# Arduino_CAN_Dev_Board.net
KiCad netlist of a schematic drawn in EAGLE
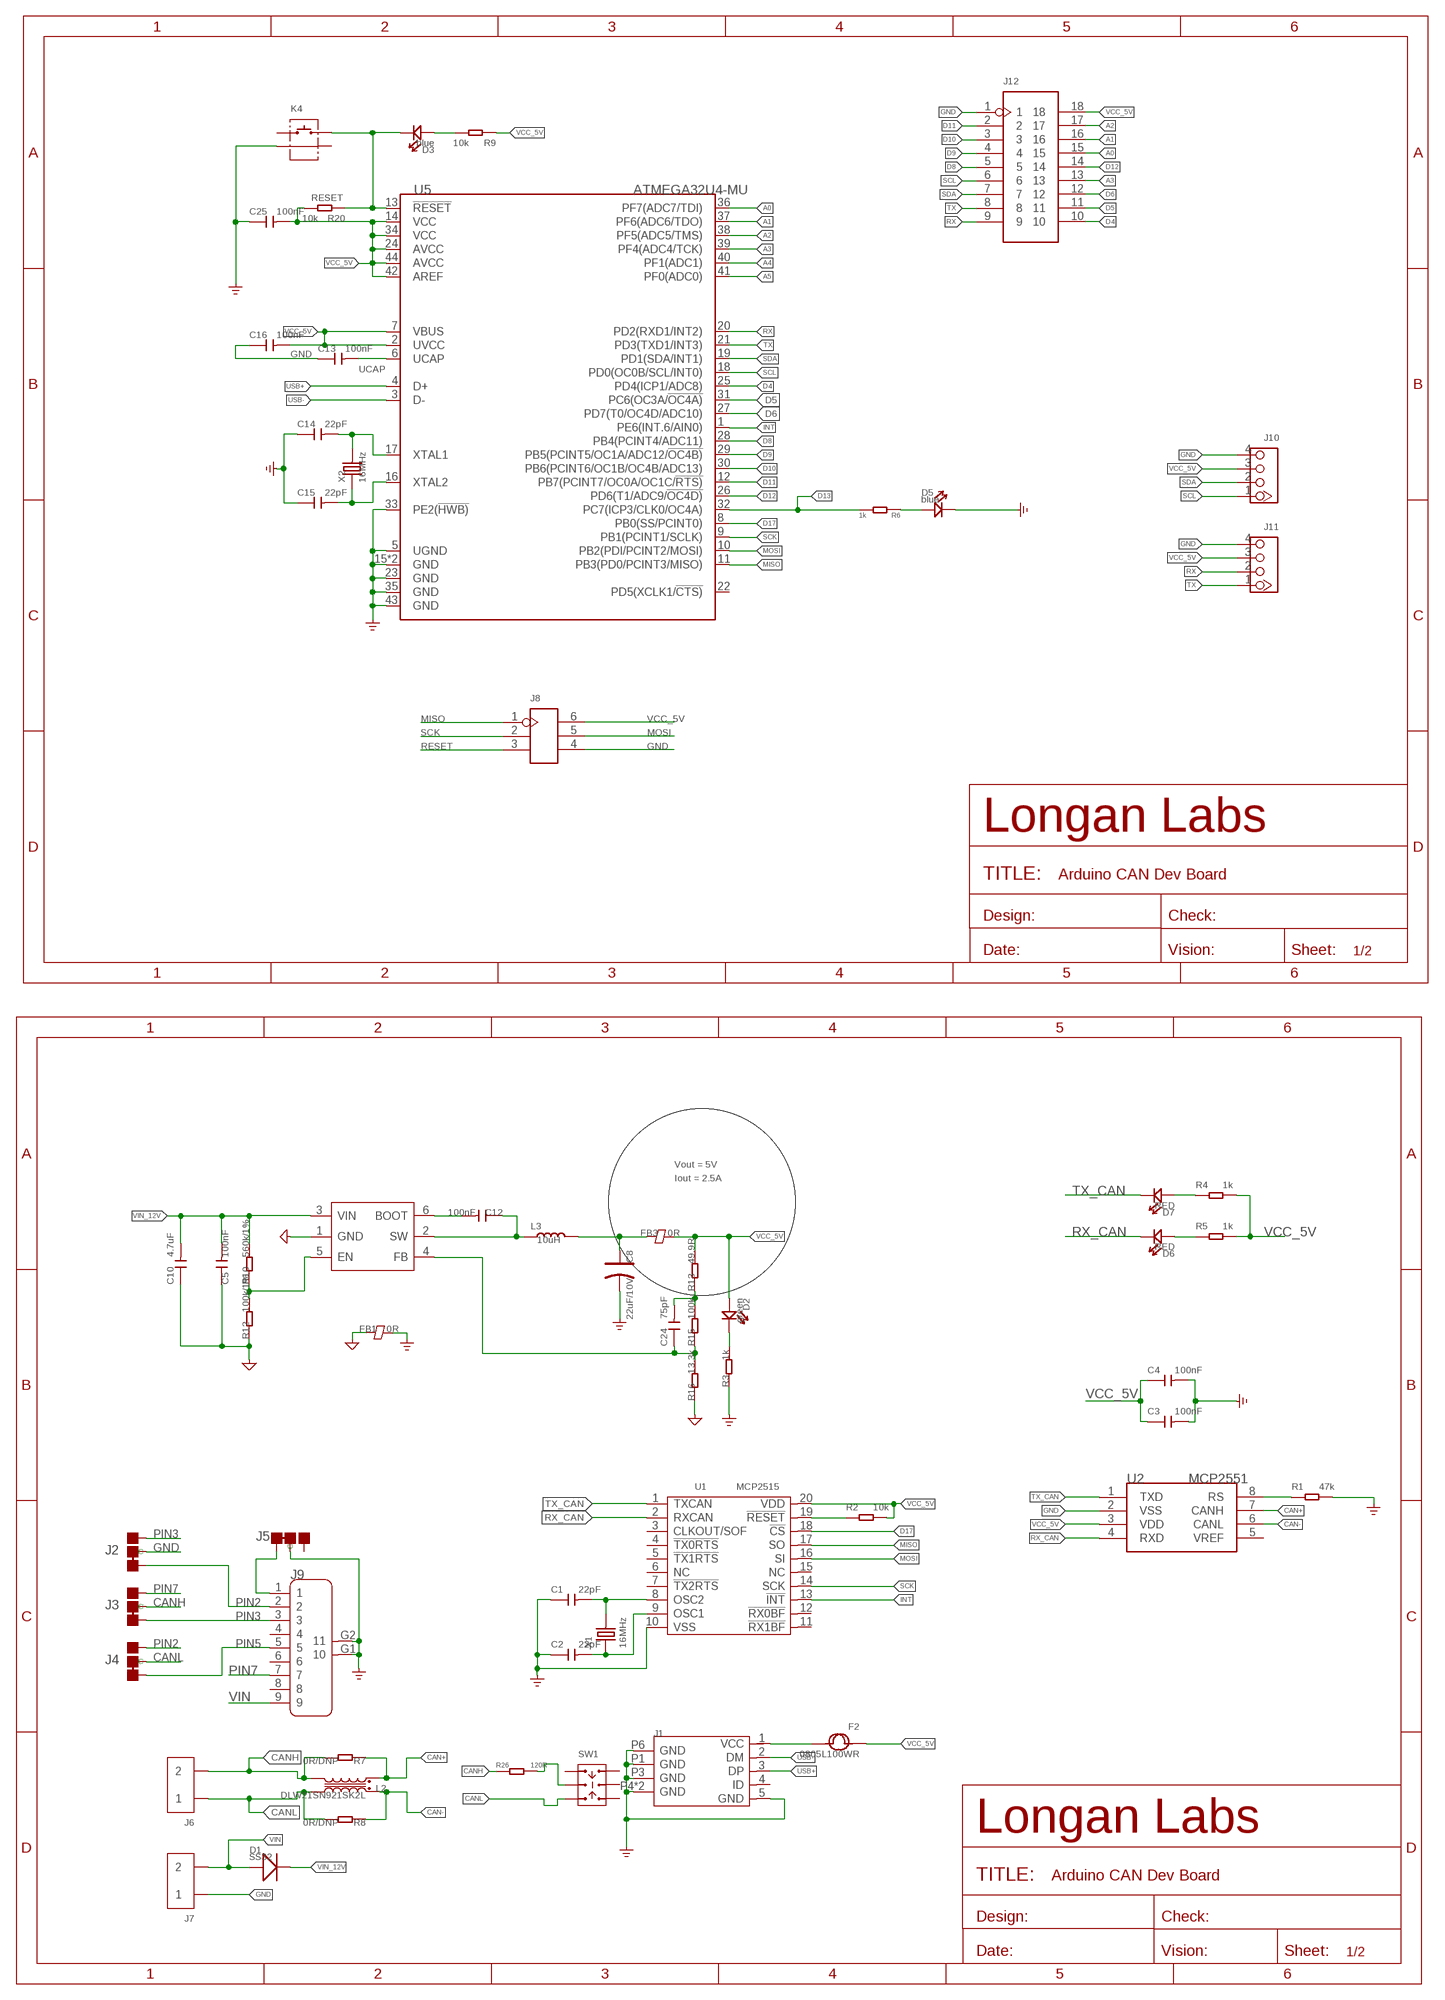
[diagram p0: schematic, sheet 1]

(export (version "E")
  (design (tool "Eeschema 10.0.6"))
  (components
    (comp (ref "C1")
      (value "22pF")
      (footprint "eagle-import:C0603")
      (libsource (lib "eagle-import") (part "CAP-0603"))
    )
    (comp (ref "C2")
      (value "22pF")
      (footprint "eagle-import:C0603")
      (libsource (lib "eagle-import") (part "CAP-0603"))
    )
    (comp (ref "C3")
      (value "100nF")
      (footprint "eagle-import:C0603")
      (libsource (lib "eagle-import") (part "CAP-0603"))
    )
    (comp (ref "C4")
      (value "100nF")
      (footprint "eagle-import:C0603")
      (libsource (lib "eagle-import") (part "CAP-0603"))
    )
    (comp (ref "C5")
      (value "100nF")
      (footprint "eagle-import:C0603")
      (libsource (lib "eagle-import") (part "CAP-0603"))
    )
    (comp (ref "C8")
      (value "22uF/10V")
      (footprint "eagle-import:AVX-B")
      (libsource (lib "eagle-import") (part "CAP-POLAR-AVX-B"))
    )
    (comp (ref "C10")
      (value "4.7uF")
      (footprint "eagle-import:C1206")
      (libsource (lib "eagle-import") (part "CAP-1206"))
    )
    (comp (ref "C12")
      (value "100nF")
      (footprint "eagle-import:C0603")
      (libsource (lib "eagle-import") (part "CAP-0603"))
    )
    (comp (ref "C13")
      (value "100nF")
      (footprint "eagle-import:C0603")
      (libsource (lib "eagle-import") (part "CAP-0603"))
    )
    (comp (ref "C14")
      (value "22pF")
      (footprint "eagle-import:C0603")
      (libsource (lib "eagle-import") (part "CAP-0603"))
    )
    (comp (ref "C15")
      (value "22pF")
      (footprint "eagle-import:C0603")
      (libsource (lib "eagle-import") (part "CAP-0603"))
    )
    (comp (ref "C16")
      (value "100nF")
      (footprint "eagle-import:C0603")
      (libsource (lib "eagle-import") (part "CAP-0603"))
    )
    (comp (ref "C24")
      (value "75pF")
      (footprint "eagle-import:C0603")
      (libsource (lib "eagle-import") (part "CAP-0603"))
    )
    (comp (ref "C25")
      (value "100nF")
      (footprint "eagle-import:C0603")
      (libsource (lib "eagle-import") (part "CAP-0603"))
    )
    (comp (ref "D1")
      (value "SS32")
      (footprint "eagle-import:DO-214AC")
      (libsource (lib "eagle-import") (part "DIODE'SMA'"))
    )
    (comp (ref "D2")
      (value "green")
      (footprint "eagle-import:LED-0603")
      (libsource (lib "eagle-import") (part "LED'0603'"))
    )
    (comp (ref "D3")
      (value "blue")
      (footprint "eagle-import:LED-0603")
      (libsource (lib "eagle-import") (part "LED'0603'"))
    )
    (comp (ref "D5")
      (value "blue")
      (footprint "eagle-import:LED-0603")
      (libsource (lib "eagle-import") (part "LED'0603'"))
    )
    (comp (ref "D6")
      (value "RED")
      (footprint "eagle-import:LED-0603")
      (libsource (lib "eagle-import") (part "LED'0603'"))
    )
    (comp (ref "D7")
      (value "RED")
      (footprint "eagle-import:LED-0603")
      (libsource (lib "eagle-import") (part "LED'0603'"))
    )
    (comp (ref "F2")
      (value "0805L100WR")
      (footprint "eagle-import:F0805")
      (libsource (lib "eagle-import") (part "FUSE0805"))
    )
    (comp (ref "FB1")
      (value "0R")
      (footprint "eagle-import:F0805")
      (libsource (lib "eagle-import") (part "FERRITE-BEAD-0805"))
    )
    (comp (ref "FB3")
      (value "0R")
      (footprint "eagle-import:F0805")
      (libsource (lib "eagle-import") (part "FERRITE-BEAD-0805"))
    )
    (comp (ref "J1")
      (value "MICRO-USB5+4P-320010050")
      (footprint "eagle-import:MICRO-USB5+5P-SMD-0.65-7.2X5.06MM")
      (libsource (lib "eagle-import") (part "MICRO-USB5+4P-320010050"))
    )
    (comp (ref "J2")
      (value "JUMPER-3P-SHORT")
      (footprint "eagle-import:3P-SMD-SHORT")
      (libsource (lib "eagle-import") (part "JUMPER-3P-SHORT"))
    )
    (comp (ref "J3")
      (value "JUMPER-3P-SHORT")
      (footprint "eagle-import:3P-SMD-SHORT")
      (libsource (lib "eagle-import") (part "JUMPER-3P-SHORT"))
    )
    (comp (ref "J4")
      (value "JUMPER-3P-SHORT")
      (footprint "eagle-import:3P-SMD-SHORT")
      (libsource (lib "eagle-import") (part "JUMPER-3P-SHORT"))
    )
    (comp (ref "J5")
      (value "JUMPER-3P-SHORT")
      (footprint "eagle-import:3P-SMD-SHORT")
      (libsource (lib "eagle-import") (part "JUMPER-3P-SHORT"))
    )
    (comp (ref "J6")
      (value "SCREW-TERMINAL-2P'5.08'")
      (footprint "eagle-import:H2-5.0-10.5X8.0MM")
      (libsource (lib "eagle-import") (part "SCREW-TERMINAL-2P'5.08'"))
    )
    (comp (ref "J7")
      (value "SCREW-TERMINAL-2P'5.08'")
      (footprint "eagle-import:H2-5.0-10.5X8.0MM")
      (libsource (lib "eagle-import") (part "SCREW-TERMINAL-2P'5.08'"))
    )
    (comp (ref "J8")
      (value "HEADER-2X3P-2.54")
      (footprint "eagle-import:H2X3-2.54")
      (libsource (lib "eagle-import") (part "HEADER-2X3P-2.54"))
    )
    (comp (ref "J9")
      (value "DB9'MEAL'")
      (footprint "eagle-import:DB9-MEAL")
      (libsource (lib "eagle-import") (part "DB9'MEAL'"))
    )
    (comp (ref "J10")
      (value "320110033")
      (footprint "eagle-import:HW4-2.0")
      (libsource (lib "eagle-import") (part "GROVE-CONNECTOR-DIP-2.0"))
    )
    (comp (ref "J11")
      (value "320110033")
      (footprint "eagle-import:HW4-2.0")
      (libsource (lib "eagle-import") (part "GROVE-CONNECTOR-DIP-2.0"))
    )
    (comp (ref "J12")
      (value "HEADER-2X9P-2.54")
      (footprint "eagle-import:H2X9-2.54")
      (libsource (lib "eagle-import") (part "HEADER-2X9P-2.54"))
    )
    (comp (ref "K4")
      (value "BUTTON-2+2P")
      (footprint "eagle-import:SW2+2P-7.7X2.75X3.95MM")
      (libsource (lib "eagle-import") (part "BUTTON-2+2P"))
    )
    (comp (ref "L2")
      (value "DLW21SN921SK2L")
      (footprint "eagle-import:INT4-0.85-2X1.25X1.2MM")
      (libsource (lib "eagle-import") (part "INDUCTOR-COMMON-MODE-SRF2012-900YA"))
    )
    (comp (ref "L3")
      (value "10uH")
      (footprint "eagle-import:INT2-SMD-6.6X7.1X3MM")
      (libsource (lib "eagle-import") (part "INDUCTOR-6.6X7.1"))
    )
    (comp (ref "R1")
      (value "47k")
      (footprint "eagle-import:R0603")
      (libsource (lib "eagle-import") (part "RES-0603"))
    )
    (comp (ref "R2")
      (value "10k")
      (footprint "eagle-import:R0603")
      (libsource (lib "eagle-import") (part "RES-0603"))
    )
    (comp (ref "R3")
      (value "1k")
      (footprint "eagle-import:R0603")
      (libsource (lib "eagle-import") (part "RES-0603"))
    )
    (comp (ref "R4")
      (value "1k")
      (footprint "eagle-import:R0603")
      (libsource (lib "eagle-import") (part "RES-0603"))
    )
    (comp (ref "R5")
      (value "1k")
      (footprint "eagle-import:R0603")
      (libsource (lib "eagle-import") (part "RES-0603"))
    )
    (comp (ref "R6")
      (value "1k")
      (footprint "eagle-import:R0603")
      (libsource (lib "eagle-import") (part "RES-0603"))
    )
    (comp (ref "R7")
      (value "0R/DNP")
      (footprint "eagle-import:R0603")
      (libsource (lib "eagle-import") (part "RES-0603"))
    )
    (comp (ref "R8")
      (value "0R/DNP")
      (footprint "eagle-import:R0603")
      (libsource (lib "eagle-import") (part "RES-0603"))
    )
    (comp (ref "R9")
      (value "10k")
      (footprint "eagle-import:R0603")
      (libsource (lib "eagle-import") (part "RES-0603"))
    )
    (comp (ref "R10")
      (value "560k/1%")
      (footprint "eagle-import:R0603")
      (libsource (lib "eagle-import") (part "RES-0603"))
    )
    (comp (ref "R12")
      (value "100k/1%")
      (footprint "eagle-import:R0603")
      (libsource (lib "eagle-import") (part "RES-0603"))
    )
    (comp (ref "R13")
      (value "49.9R")
      (footprint "eagle-import:R0603")
      (libsource (lib "eagle-import") (part "RES-0603"))
    )
    (comp (ref "R15")
      (value "100k")
      (footprint "eagle-import:R0603")
      (libsource (lib "eagle-import") (part "RES-0603"))
    )
    (comp (ref "R16")
      (value "13.3k")
      (footprint "eagle-import:R0603")
      (libsource (lib "eagle-import") (part "RES-0603"))
    )
    (comp (ref "R20")
      (value "10k")
      (footprint "eagle-import:R0603")
      (libsource (lib "eagle-import") (part "RES-0603"))
    )
    (comp (ref "R26")
      (value "120R")
      (footprint "eagle-import:R0603")
      (libsource (lib "eagle-import") (part "RES-0603"))
    )
    (comp (ref "SW1")
      (value "SWITCH-2CH-6P-311010004")
      (footprint "eagle-import:SW6-2.54-9.0X3.5X3.2+2.0MM")
      (libsource (lib "eagle-import") (part "SWITCH-2CH-6P-311010004"))
    )
    (comp (ref "U$11")
      (value "PMIC-TPS54302")
      (footprint "eagle-import:SOT-23-6")
      (libsource (lib "eagle-import") (part "PMIC-TPS54302"))
    )
    (comp (ref "U1")
      (value "MCP2515")
      (footprint "eagle-import:TSSOP20-0.65-6.5X4.4MM")
      (libsource (lib "eagle-import") (part "MCP2515'ST'"))
    )
    (comp (ref "U2")
      (value "MCP2551")
      (footprint "eagle-import:SOIC8-6.0")
      (libsource (lib "eagle-import") (part "MCP2551-SOIC8"))
    )
    (comp (ref "U5")
      (value "ATMEGA32U4-MU")
      (footprint "eagle-import:QFN44")
      (libsource (lib "eagle-import") (part "ATMEGA32U4-MU"))
    )
    (comp (ref "X1")
      (value "16MHz")
      (footprint "eagle-import:X2-SMD-5.0X3.2X1.3MM")
      (libsource (lib "eagle-import") (part "CRYSTAL-2P'5032'"))
    )
    (comp (ref "X2")
      (value "16MHz")
      (footprint "eagle-import:2P-SMD-5X3.2")
      (libsource (lib "eagle-import") (part "CRYSTAL'5032'"))
    )
  )
  (nets
    (net (code "1") (name "A0") (class "Default")
      (node (ref "J12") (pin "15") (pinfunction "15_15") (pintype "bidirectional"))
      (node (ref "U5") (pin "36") (pinfunction "PF7(ADC7/TDI)_36") (pintype "bidirectional"))
    )
    (net (code "2") (name "A1") (class "Default")
      (node (ref "J12") (pin "16") (pinfunction "16_16") (pintype "bidirectional"))
      (node (ref "U5") (pin "37") (pinfunction "PF6(ADC6/TDO)_37") (pintype "bidirectional"))
    )
    (net (code "3") (name "A2") (class "Default")
      (node (ref "J12") (pin "17") (pinfunction "17_17") (pintype "bidirectional"))
      (node (ref "U5") (pin "38") (pinfunction "PF5(ADC5/TMS)_38") (pintype "bidirectional"))
    )
    (net (code "4") (name "A3") (class "Default")
      (node (ref "J12") (pin "13") (pinfunction "13_13") (pintype "bidirectional"))
      (node (ref "U5") (pin "39") (pinfunction "PF4(ADC4/TCK)_39") (pintype "bidirectional"))
    )
    (net (code "5") (name "A4") (class "Default")
      (node (ref "U5") (pin "40") (pinfunction "PF1(ADC1)_40") (pintype "bidirectional"))
    )
    (net (code "6") (name "A5") (class "Default")
      (node (ref "U5") (pin "41") (pinfunction "PF0(ADC0)_41") (pintype "bidirectional"))
    )
    (net (code "7") (name "AGND") (class "Default")
      (node (ref "C10") (pin "1") (pinfunction "1_1") (pintype "passive"))
      (node (ref "C5") (pin "1") (pinfunction "1_1") (pintype "passive"))
      (node (ref "FB1") (pin "1") (pinfunction "1_1") (pintype "bidirectional"))
      (node (ref "R12") (pin "1") (pinfunction "1_1") (pintype "passive"))
      (node (ref "R16") (pin "1") (pinfunction "1_1") (pintype "passive"))
      (node (ref "U$11") (pin "1") (pinfunction "GND_1") (pintype "bidirectional"))
    )
    (net (code "8") (name "CAN+") (class "Default")
      (node (ref "L2") (pin "4") (pinfunction "4_4") (pintype "bidirectional"))
      (node (ref "R7") (pin "1") (pinfunction "1_1") (pintype "passive"))
      (node (ref "U2") (pin "7") (pinfunction "CANH_7") (pintype "bidirectional"))
    )
    (net (code "9") (name "CAN-") (class "Default")
      (node (ref "L2") (pin "1") (pinfunction "1_1") (pintype "bidirectional"))
      (node (ref "R8") (pin "1") (pinfunction "1_1") (pintype "passive"))
      (node (ref "U2") (pin "6") (pinfunction "CANL_6") (pintype "bidirectional"))
    )
    (net (code "10") (name "CANH") (class "Default")
      (node (ref "J3") (pin "MM") (pinfunction "C_MM") (pintype "bidirectional"))
      (node (ref "J6") (pin "2") (pinfunction "2_2") (pintype "bidirectional"))
      (node (ref "L2") (pin "3") (pinfunction "3_3") (pintype "bidirectional"))
      (node (ref "R26") (pin "1") (pinfunction "1_1") (pintype "passive"))
      (node (ref "R7") (pin "2") (pinfunction "2_2") (pintype "passive"))
    )
    (net (code "11") (name "CANL") (class "Default")
      (node (ref "J4") (pin "MM") (pinfunction "C_MM") (pintype "bidirectional"))
      (node (ref "J6") (pin "1") (pinfunction "1_1") (pintype "bidirectional"))
      (node (ref "L2") (pin "2") (pinfunction "2_2") (pintype "bidirectional"))
      (node (ref "R8") (pin "2") (pinfunction "2_2") (pintype "passive"))
      (node (ref "SW1") (pin "CH1B") (pinfunction "CH1B_CH1B") (pintype "bidirectional"))
    )
    (net (code "12") (name "D4") (class "Default")
      (node (ref "J12") (pin "10") (pinfunction "10_10") (pintype "bidirectional"))
      (node (ref "U5") (pin "25") (pinfunction "PD4(ICP1/ADC8)_25") (pintype "bidirectional"))
    )
    (net (code "13") (name "D5") (class "Default")
      (node (ref "J12") (pin "11") (pinfunction "11_11") (pintype "bidirectional"))
      (node (ref "U5") (pin "31") (pinfunction "PC6(OC3A/~{OC4A})_31") (pintype "bidirectional"))
    )
    (net (code "14") (name "D6") (class "Default")
      (node (ref "J12") (pin "12") (pinfunction "12_12") (pintype "bidirectional"))
      (node (ref "U5") (pin "27") (pinfunction "PD7(T0/OC4D/ADC10)_27") (pintype "bidirectional"))
    )
    (net (code "15") (name "D8") (class "Default")
      (node (ref "J12") (pin "5") (pinfunction "5_5") (pintype "bidirectional"))
      (node (ref "U5") (pin "28") (pinfunction "PB4(PCINT4/ADC11)_28") (pintype "bidirectional"))
    )
    (net (code "16") (name "D9") (class "Default")
      (node (ref "J12") (pin "4") (pinfunction "4_4") (pintype "bidirectional"))
      (node (ref "U5") (pin "29") (pinfunction "PB5(PCINT5/OC1A/ADC12/~{OC4B})_29") (pintype "bidirectional"))
    )
    (net (code "17") (name "D10") (class "Default")
      (node (ref "J12") (pin "3") (pinfunction "3_3") (pintype "bidirectional"))
      (node (ref "U5") (pin "30") (pinfunction "PB6(PCINT6/OC1B/OC4B/ADC13)_30") (pintype "bidirectional"))
    )
    (net (code "18") (name "D11") (class "Default")
      (node (ref "J12") (pin "2") (pinfunction "2_2") (pintype "bidirectional"))
      (node (ref "U5") (pin "12") (pinfunction "PB7(PCINT7/OC0A/OC1C/~{RTS})_12") (pintype "bidirectional"))
    )
    (net (code "19") (name "D12") (class "Default")
      (node (ref "J12") (pin "14") (pinfunction "14_14") (pintype "bidirectional"))
      (node (ref "U5") (pin "26") (pinfunction "PD6(T1/ADC9/~{OC4D})_26") (pintype "bidirectional"))
    )
    (net (code "20") (name "D13") (class "Default")
      (node (ref "R6") (pin "2") (pinfunction "2_2") (pintype "passive"))
      (node (ref "U5") (pin "32") (pinfunction "PC7(ICP3/CLK0/OC4A)_32") (pintype "bidirectional"))
    )
    (net (code "21") (name "D17") (class "Default")
      (node (ref "U1") (pin "18") (pinfunction "~{CS}_18") (pintype "bidirectional"))
      (node (ref "U5") (pin "8") (pinfunction "PB0(SS/PCINT0)_8") (pintype "bidirectional"))
    )
    (net (code "22") (name "GND") (class "Default")
      (node (ref "C1") (pin "1") (pinfunction "1_1") (pintype "passive"))
      (node (ref "C13") (pin "1") (pinfunction "1_1") (pintype "passive"))
      (node (ref "C14") (pin "1") (pinfunction "1_1") (pintype "passive"))
      (node (ref "C15") (pin "1") (pinfunction "1_1") (pintype "passive"))
      (node (ref "C16") (pin "1") (pinfunction "1_1") (pintype "passive"))
      (node (ref "C2") (pin "1") (pinfunction "1_1") (pintype "passive"))
      (node (ref "C25") (pin "1") (pinfunction "1_1") (pintype "passive"))
      (node (ref "C3") (pin "2") (pinfunction "2_2") (pintype "passive"))
      (node (ref "C4") (pin "2") (pinfunction "2_2") (pintype "passive"))
      (node (ref "C8") (pin "-") (pinfunction "-_-") (pintype "passive"))
      (node (ref "D5") (pin "-") (pinfunction "-_-") (pintype "passive"))
      (node (ref "FB1") (pin "2") (pinfunction "2_2") (pintype "bidirectional"))
      (node (ref "J1") (pin "5") (pinfunction "GND_5") (pintype "bidirectional"))
      (node (ref "J1") (pin "P1") (pinfunction "GND_P1") (pintype "bidirectional"))
      (node (ref "J1") (pin "P3") (pinfunction "GND_P3") (pintype "bidirectional"))
      (node (ref "J1") (pin "P4") (pinfunction "GND_P4") (pintype "bidirectional"))
      (node (ref "J1") (pin "P5") (pinfunction "GND_P5") (pintype "bidirectional"))
      (node (ref "J1") (pin "P6") (pinfunction "GND_P6") (pintype "bidirectional"))
      (node (ref "J10") (pin "4") (pinfunction "4_4") (pintype "bidirectional"))
      (node (ref "J11") (pin "4") (pinfunction "4_4") (pintype "bidirectional"))
      (node (ref "J12") (pin "1") (pinfunction "1_1") (pintype "bidirectional"))
      (node (ref "J2") (pin "MM") (pinfunction "C_MM") (pintype "bidirectional"))
      (node (ref "J5") (pin "MM") (pinfunction "C_MM") (pintype "bidirectional"))
      (node (ref "J7") (pin "1") (pinfunction "1_1") (pintype "bidirectional"))
      (node (ref "J8") (pin "4") (pinfunction "4_4") (pintype "bidirectional"))
      (node (ref "J9") (pin "G1") (pinfunction "10_G1") (pintype "bidirectional"))
      (node (ref "J9") (pin "G2") (pinfunction "11_G2") (pintype "bidirectional"))
      (node (ref "K4") (pin "S1") (pinfunction "S1_S1") (pintype "bidirectional"))
      (node (ref "R1") (pin "2") (pinfunction "2_2") (pintype "passive"))
      (node (ref "R3") (pin "1") (pinfunction "1_1") (pintype "passive"))
      (node (ref "U1") (pin "10") (pinfunction "VSS_10") (pintype "bidirectional"))
      (node (ref "U2") (pin "2") (pinfunction "VSS_2") (pintype "bidirectional"))
      (node (ref "U5") (pin "15") (pinfunction "GND_15") (pintype "bidirectional"))
      (node (ref "U5") (pin "23") (pinfunction "GND_23") (pintype "bidirectional"))
      (node (ref "U5") (pin "33") (pinfunction "PE2(~{HWB})_33") (pintype "bidirectional"))
      (node (ref "U5") (pin "35") (pinfunction "GND_35") (pintype "bidirectional"))
      (node (ref "U5") (pin "43") (pinfunction "GND_43") (pintype "bidirectional"))
      (node (ref "U5") (pin "5") (pinfunction "UGND_5") (pintype "bidirectional"))
      (node (ref "U5") (pin "TAB") (pinfunction "GND_TAB") (pintype "bidirectional"))
    )
    (net (code "23") (name "INT") (class "Default")
      (node (ref "U1") (pin "13") (pinfunction "~{INT}_13") (pintype "bidirectional"))
      (node (ref "U5") (pin "1") (pinfunction "PE6(INT.6/AIN0)_1") (pintype "bidirectional"))
    )
    (net (code "24") (name "MISO") (class "Default")
      (node (ref "J8") (pin "1") (pinfunction "1_1") (pintype "bidirectional"))
      (node (ref "U1") (pin "17") (pinfunction "SO_17") (pintype "bidirectional"))
      (node (ref "U5") (pin "11") (pinfunction "PB3(PD0/PCINT3/MISO)_11") (pintype "bidirectional"))
    )
    (net (code "25") (name "MOSI") (class "Default")
      (node (ref "J8") (pin "5") (pinfunction "5_5") (pintype "bidirectional"))
      (node (ref "U1") (pin "16") (pinfunction "SI_16") (pintype "bidirectional"))
      (node (ref "U5") (pin "10") (pinfunction "PB2(PDI/PCINT2/MOSI)_10") (pintype "bidirectional"))
    )
    (net (code "26") (name "Net-(C8-Pad+)") (class "Default")
      (node (ref "C8") (pin "+") (pinfunction "+_+") (pintype "passive"))
      (node (ref "FB3") (pin "1") (pinfunction "1_1") (pintype "bidirectional"))
      (node (ref "L3") (pin "2") (pinfunction "2_2") (pintype "passive"))
    )
    (net (code "27") (name "Net-(C24-Pad2)") (class "Default")
      (node (ref "C24") (pin "2") (pinfunction "2_2") (pintype "passive"))
      (node (ref "R13") (pin "1") (pinfunction "1_1") (pintype "passive"))
      (node (ref "R15") (pin "2") (pinfunction "2_2") (pintype "passive"))
    )
    (net (code "28") (name "Net-(D2-Pad-)") (class "Default")
      (node (ref "D2") (pin "-") (pinfunction "-_-") (pintype "passive"))
      (node (ref "R3") (pin "2") (pinfunction "2_2") (pintype "passive"))
    )
    (net (code "29") (name "Net-(D3-Pad+)") (class "Default")
      (node (ref "D3") (pin "+") (pinfunction "+_+") (pintype "passive"))
      (node (ref "R9") (pin "2") (pinfunction "2_2") (pintype "passive"))
    )
    (net (code "30") (name "Net-(D5-Pad+)") (class "Default")
      (node (ref "D5") (pin "+") (pinfunction "+_+") (pintype "passive"))
      (node (ref "R6") (pin "1") (pinfunction "1_1") (pintype "passive"))
    )
    (net (code "31") (name "Net-(D6-Pad+)") (class "Default")
      (node (ref "D6") (pin "+") (pinfunction "+_+") (pintype "passive"))
      (node (ref "R5") (pin "1") (pinfunction "1_1") (pintype "passive"))
    )
    (net (code "32") (name "Net-(D7-Pad+)") (class "Default")
      (node (ref "D7") (pin "+") (pinfunction "+_+") (pintype "passive"))
      (node (ref "R4") (pin "1") (pinfunction "1_1") (pintype "passive"))
    )
    (net (code "33") (name "Net-(J1-VCC)") (class "Default")
      (node (ref "F2") (pin "2") (pinfunction "2_2") (pintype "bidirectional"))
      (node (ref "J1") (pin "1") (pinfunction "VCC_1") (pintype "bidirectional"))
    )
    (net (code "34") (name "Net-(J5-L)") (class "Default")
      (node (ref "J5") (pin "11") (pinfunction "L_11") (pintype "bidirectional"))
      (node (ref "J9") (pin "1") (pinfunction "1_1") (pintype "bidirectional"))
    )
    (net (code "35") (name "Net-(R26-Pad2)") (class "Default")
      (node (ref "R26") (pin "2") (pinfunction "2_2") (pintype "passive"))
      (node (ref "SW1") (pin "COM1") (pinfunction "COM1_COM1") (pintype "bidirectional"))
    )
    (net (code "36") (name "Net-(U$11-BOOT)") (class "Default")
      (node (ref "C12") (pin "2") (pinfunction "2_2") (pintype "passive"))
      (node (ref "U$11") (pin "6") (pinfunction "BOOT_6") (pintype "bidirectional"))
    )
    (net (code "37") (name "Net-(U$11-EN)") (class "Default")
      (node (ref "R10") (pin "1") (pinfunction "1_1") (pintype "passive"))
      (node (ref "R12") (pin "2") (pinfunction "2_2") (pintype "passive"))
      (node (ref "U$11") (pin "5") (pinfunction "EN_5") (pintype "bidirectional"))
    )
    (net (code "38") (name "Net-(U$11-FB)") (class "Default")
      (node (ref "C24") (pin "1") (pinfunction "1_1") (pintype "passive"))
      (node (ref "R15") (pin "1") (pinfunction "1_1") (pintype "passive"))
      (node (ref "R16") (pin "2") (pinfunction "2_2") (pintype "passive"))
      (node (ref "U$11") (pin "4") (pinfunction "FB_4") (pintype "bidirectional"))
    )
    (net (code "39") (name "Net-(U$11-SW)") (class "Default")
      (node (ref "C12") (pin "1") (pinfunction "1_1") (pintype "passive"))
      (node (ref "L3") (pin "1") (pinfunction "1_1") (pintype "passive"))
      (node (ref "U$11") (pin "2") (pinfunction "SW_2") (pintype "bidirectional"))
    )
    (net (code "40") (name "Net-(U1-OSC1)") (class "Default")
      (node (ref "C2") (pin "2") (pinfunction "2_2") (pintype "passive"))
      (node (ref "U1") (pin "9") (pinfunction "OSC1_9") (pintype "bidirectional"))
      (node (ref "X1") (pin "1") (pinfunction "1_1") (pintype "passive"))
    )
    (net (code "41") (name "Net-(U1-OSC2)") (class "Default")
      (node (ref "C1") (pin "2") (pinfunction "2_2") (pintype "passive"))
      (node (ref "U1") (pin "8") (pinfunction "OSC2_8") (pintype "bidirectional"))
      (node (ref "X1") (pin "2") (pinfunction "2_2") (pintype "passive"))
    )
    (net (code "42") (name "Net-(U1-~{RESET})") (class "Default")
      (node (ref "R2") (pin "1") (pinfunction "1_1") (pintype "passive"))
      (node (ref "U1") (pin "19") (pinfunction "~{RESET}_19") (pintype "bidirectional"))
    )
    (net (code "43") (name "Net-(U2-RS)") (class "Default")
      (node (ref "R1") (pin "1") (pinfunction "1_1") (pintype "passive"))
      (node (ref "U2") (pin "8") (pinfunction "RS_8") (pintype "bidirectional"))
    )
    (net (code "44") (name "Net-(U5-XTAL1)") (class "Default")
      (node (ref "C14") (pin "2") (pinfunction "2_2") (pintype "passive"))
      (node (ref "U5") (pin "17") (pinfunction "XTAL1_17") (pintype "bidirectional"))
      (node (ref "X2") (pin "2") (pinfunction "2_2") (pintype "passive"))
    )
    (net (code "45") (name "Net-(U5-XTAL2)") (class "Default")
      (node (ref "C15") (pin "2") (pinfunction "2_2") (pintype "passive"))
      (node (ref "U5") (pin "16") (pinfunction "XTAL2_16") (pintype "bidirectional"))
      (node (ref "X2") (pin "1") (pinfunction "1_1") (pintype "passive"))
    )
    (net (code "46") (name "PIN2") (class "Default")
      (node (ref "J2") (pin "11") (pinfunction "L_11") (pintype "bidirectional"))
      (node (ref "J4") (pin "00") (pinfunction "R_00") (pintype "bidirectional"))
      (node (ref "J9") (pin "2") (pinfunction "2_2") (pintype "bidirectional"))
    )
    (net (code "47") (name "PIN3") (class "Default")
      (node (ref "J2") (pin "00") (pinfunction "R_00") (pintype "bidirectional"))
      (node (ref "J3") (pin "11") (pinfunction "L_11") (pintype "bidirectional"))
      (node (ref "J9") (pin "3") (pinfunction "3_3") (pintype "bidirectional"))
    )
    (net (code "48") (name "PIN5") (class "Default")
      (node (ref "J4") (pin "11") (pinfunction "L_11") (pintype "bidirectional"))
      (node (ref "J9") (pin "5") (pinfunction "5_5") (pintype "bidirectional"))
    )
    (net (code "49") (name "PIN7") (class "Default")
      (node (ref "J3") (pin "00") (pinfunction "R_00") (pintype "bidirectional"))
      (node (ref "J9") (pin "7") (pinfunction "7_7") (pintype "bidirectional"))
    )
    (net (code "50") (name "RESET") (class "Default")
      (node (ref "D3") (pin "-") (pinfunction "-_-") (pintype "passive"))
      (node (ref "J8") (pin "3") (pinfunction "3_3") (pintype "bidirectional"))
      (node (ref "K4") (pin "2") (pinfunction "2_2") (pintype "bidirectional"))
      (node (ref "R20") (pin "1") (pinfunction "1_1") (pintype "passive"))
      (node (ref "U5") (pin "13") (pinfunction "~{RESET}_13") (pintype "bidirectional"))
    )
    (net (code "51") (name "RX") (class "Default")
      (node (ref "J11") (pin "2") (pinfunction "2_2") (pintype "bidirectional"))
      (node (ref "J12") (pin "9") (pinfunction "9_9") (pintype "bidirectional"))
      (node (ref "U5") (pin "20") (pinfunction "PD2(RXD1/INT2)_20") (pintype "bidirectional"))
    )
    (net (code "52") (name "RX_CAN") (class "Default")
      (node (ref "D6") (pin "-") (pinfunction "-_-") (pintype "passive"))
      (node (ref "U1") (pin "2") (pinfunction "RXCAN_2") (pintype "bidirectional"))
      (node (ref "U2") (pin "4") (pinfunction "RXD_4") (pintype "bidirectional"))
    )
    (net (code "53") (name "SCK") (class "Default")
      (node (ref "J8") (pin "2") (pinfunction "2_2") (pintype "bidirectional"))
      (node (ref "U1") (pin "14") (pinfunction "SCK_14") (pintype "bidirectional"))
      (node (ref "U5") (pin "9") (pinfunction "PB1(PCINT1/SCLK)_9") (pintype "bidirectional"))
    )
    (net (code "54") (name "SCL") (class "Default")
      (node (ref "J10") (pin "1") (pinfunction "1_1") (pintype "bidirectional"))
      (node (ref "J12") (pin "6") (pinfunction "6_6") (pintype "bidirectional"))
      (node (ref "U5") (pin "18") (pinfunction "PD0(OC0B/SCL/INT0)_18") (pintype "bidirectional"))
    )
    (net (code "55") (name "SDA") (class "Default")
      (node (ref "J10") (pin "2") (pinfunction "2_2") (pintype "bidirectional"))
      (node (ref "J12") (pin "7") (pinfunction "7_7") (pintype "bidirectional"))
      (node (ref "U5") (pin "19") (pinfunction "PD1(SDA/INT1)_19") (pintype "bidirectional"))
    )
    (net (code "56") (name "TX") (class "Default")
      (node (ref "J11") (pin "1") (pinfunction "1_1") (pintype "bidirectional"))
      (node (ref "J12") (pin "8") (pinfunction "8_8") (pintype "bidirectional"))
      (node (ref "U5") (pin "21") (pinfunction "PD3(TXD1/INT3)_21") (pintype "bidirectional"))
    )
    (net (code "57") (name "TX_CAN") (class "Default")
      (node (ref "D7") (pin "-") (pinfunction "-_-") (pintype "passive"))
      (node (ref "U1") (pin "1") (pinfunction "TXCAN_1") (pintype "bidirectional"))
      (node (ref "U2") (pin "1") (pinfunction "TXD_1") (pintype "bidirectional"))
    )
    (net (code "58") (name "UCAP") (class "Default")
      (node (ref "C13") (pin "2") (pinfunction "2_2") (pintype "passive"))
      (node (ref "U5") (pin "6") (pinfunction "UCAP_6") (pintype "bidirectional"))
    )
    (net (code "59") (name "USB+") (class "Default")
      (node (ref "J1") (pin "3") (pinfunction "DP_3") (pintype "bidirectional"))
      (node (ref "U5") (pin "4") (pinfunction "D+_4") (pintype "bidirectional"))
    )
    (net (code "60") (name "USB-") (class "Default")
      (node (ref "J1") (pin "2") (pinfunction "DM_2") (pintype "bidirectional"))
      (node (ref "U5") (pin "3") (pinfunction "D-_3") (pintype "bidirectional"))
    )
    (net (code "61") (name "VCC_5V") (class "Default")
      (node (ref "C16") (pin "2") (pinfunction "2_2") (pintype "passive"))
      (node (ref "C25") (pin "2") (pinfunction "2_2") (pintype "passive"))
      (node (ref "C3") (pin "1") (pinfunction "1_1") (pintype "passive"))
      (node (ref "C4") (pin "1") (pinfunction "1_1") (pintype "passive"))
      (node (ref "D2") (pin "+") (pinfunction "+_+") (pintype "passive"))
      (node (ref "F2") (pin "1") (pinfunction "1_1") (pintype "bidirectional"))
      (node (ref "FB3") (pin "2") (pinfunction "2_2") (pintype "bidirectional"))
      (node (ref "J10") (pin "3") (pinfunction "3_3") (pintype "bidirectional"))
      (node (ref "J11") (pin "3") (pinfunction "3_3") (pintype "bidirectional"))
      (node (ref "J12") (pin "18") (pinfunction "18_18") (pintype "bidirectional"))
      (node (ref "J8") (pin "6") (pinfunction "6_6") (pintype "bidirectional"))
      (node (ref "R13") (pin "2") (pinfunction "2_2") (pintype "passive"))
      (node (ref "R2") (pin "2") (pinfunction "2_2") (pintype "passive"))
      (node (ref "R20") (pin "2") (pinfunction "2_2") (pintype "passive"))
      (node (ref "R4") (pin "2") (pinfunction "2_2") (pintype "passive"))
      (node (ref "R5") (pin "2") (pinfunction "2_2") (pintype "passive"))
      (node (ref "R9") (pin "1") (pinfunction "1_1") (pintype "passive"))
      (node (ref "U1") (pin "20") (pinfunction "VDD_20") (pintype "bidirectional"))
      (node (ref "U2") (pin "3") (pinfunction "VDD_3") (pintype "bidirectional"))
      (node (ref "U5") (pin "14") (pinfunction "VCC_14") (pintype "bidirectional"))
      (node (ref "U5") (pin "2") (pinfunction "UVCC_2") (pintype "bidirectional"))
      (node (ref "U5") (pin "24") (pinfunction "AVCC_24") (pintype "bidirectional"))
      (node (ref "U5") (pin "34") (pinfunction "VCC_34") (pintype "bidirectional"))
      (node (ref "U5") (pin "42") (pinfunction "AREF_42") (pintype "bidirectional"))
      (node (ref "U5") (pin "44") (pinfunction "AVCC_44") (pintype "bidirectional"))
      (node (ref "U5") (pin "7") (pinfunction "VBUS_7") (pintype "bidirectional"))
    )
    (net (code "62") (name "VIN") (class "Default")
      (node (ref "D1") (pin "1") (pinfunction "+_1") (pintype "passive"))
      (node (ref "J7") (pin "2") (pinfunction "2_2") (pintype "bidirectional"))
      (node (ref "J9") (pin "9") (pinfunction "9_9") (pintype "bidirectional"))
    )
    (net (code "63") (name "VIN_12V") (class "Default")
      (node (ref "C10") (pin "2") (pinfunction "2_2") (pintype "passive"))
      (node (ref "C5") (pin "2") (pinfunction "2_2") (pintype "passive"))
      (node (ref "D1") (pin "2") (pinfunction "-_2") (pintype "passive"))
      (node (ref "R10") (pin "2") (pinfunction "2_2") (pintype "passive"))
      (node (ref "U$11") (pin "3") (pinfunction "VIN_3") (pintype "bidirectional"))
    )
    (net (code "64") (name "unconnected-(J1-ID-Pad4)") (class "Default")
      (node (ref "J1") (pin "4") (pinfunction "ID_4") (pintype "bidirectional"))
    )
    (net (code "65") (name "unconnected-(J5-R-Pad00)") (class "Default")
      (node (ref "J5") (pin "00") (pinfunction "R_00") (pintype "bidirectional"))
    )
    (net (code "66") (name "unconnected-(J9-Pad4)") (class "Default")
      (node (ref "J9") (pin "4") (pinfunction "4_4") (pintype "bidirectional"))
    )
    (net (code "67") (name "unconnected-(J9-Pad6)") (class "Default")
      (node (ref "J9") (pin "6") (pinfunction "6_6") (pintype "bidirectional"))
    )
    (net (code "68") (name "unconnected-(J9-Pad8)") (class "Default")
      (node (ref "J9") (pin "8") (pinfunction "8_8") (pintype "bidirectional"))
    )
    (net (code "69") (name "unconnected-(K4-Pad1)") (class "Default")
      (node (ref "K4") (pin "1") (pinfunction "1_1") (pintype "bidirectional"))
    )
    (net (code "70") (name "unconnected-(K4-PadS2)") (class "Default")
      (node (ref "K4") (pin "S2") (pinfunction "S2_S2") (pintype "bidirectional"))
    )
    (net (code "71") (name "unconnected-(SW1-PadCH1A)") (class "Default")
      (node (ref "SW1") (pin "CH1A") (pinfunction "CH1A_CH1A") (pintype "bidirectional"))
    )
    (net (code "72") (name "unconnected-(SW1-PadCH2A)") (class "Default")
      (node (ref "SW1") (pin "CH2A") (pinfunction "CH2A_CH2A") (pintype "bidirectional"))
    )
    (net (code "73") (name "unconnected-(SW1-PadCH2B)") (class "Default")
      (node (ref "SW1") (pin "CH2B") (pinfunction "CH2B_CH2B") (pintype "bidirectional"))
    )
    (net (code "74") (name "unconnected-(SW1-PadCOM2)") (class "Default")
      (node (ref "SW1") (pin "COM2") (pinfunction "COM2_COM2") (pintype "bidirectional"))
    )
    (net (code "75") (name "unconnected-(U1-CLKOUT{slash}SOF-Pad3)") (class "Default")
      (node (ref "U1") (pin "3") (pinfunction "CLKOUT/SOF_3") (pintype "bidirectional"))
    )
    (net (code "76") (name "unconnected-(U1-NC-Pad6)") (class "Default")
      (node (ref "U1") (pin "6") (pinfunction "NC_6") (pintype "bidirectional"))
    )
    (net (code "77") (name "unconnected-(U1-NC-Pad15)") (class "Default")
      (node (ref "U1") (pin "15") (pinfunction "NC_15") (pintype "bidirectional"))
    )
    (net (code "78") (name "unconnected-(U1-~{RX0BF}-Pad12)") (class "Default")
      (node (ref "U1") (pin "12") (pinfunction "~{RX0BF}_12") (pintype "bidirectional"))
    )
    (net (code "79") (name "unconnected-(U1-~{RX1BF}-Pad11)") (class "Default")
      (node (ref "U1") (pin "11") (pinfunction "~{RX1BF}_11") (pintype "bidirectional"))
    )
    (net (code "80") (name "unconnected-(U1-~{TX0RTS}-Pad4)") (class "Default")
      (node (ref "U1") (pin "4") (pinfunction "~{TX0RTS}_4") (pintype "bidirectional"))
    )
    (net (code "81") (name "unconnected-(U1-~{TX1RTS}-Pad5)") (class "Default")
      (node (ref "U1") (pin "5") (pinfunction "~{TX1RTS}_5") (pintype "bidirectional"))
    )
    (net (code "82") (name "unconnected-(U1-~{TX2RTS}-Pad7)") (class "Default")
      (node (ref "U1") (pin "7") (pinfunction "~{TX2RTS}_7") (pintype "bidirectional"))
    )
    (net (code "83") (name "unconnected-(U2-VREF-Pad5)") (class "Default")
      (node (ref "U2") (pin "5") (pinfunction "VREF_5") (pintype "bidirectional"))
    )
    (net (code "84") (name "unconnected-(U5-PD5(XCLK1{slash}~{CTS})-Pad22)") (class "Default")
      (node (ref "U5") (pin "22") (pinfunction "PD5(XCLK1/~{CTS})_22") (pintype "bidirectional"))
    )
  )
)
